# lpcCNC.net
KiCad netlist of a schematic drawn in EAGLE
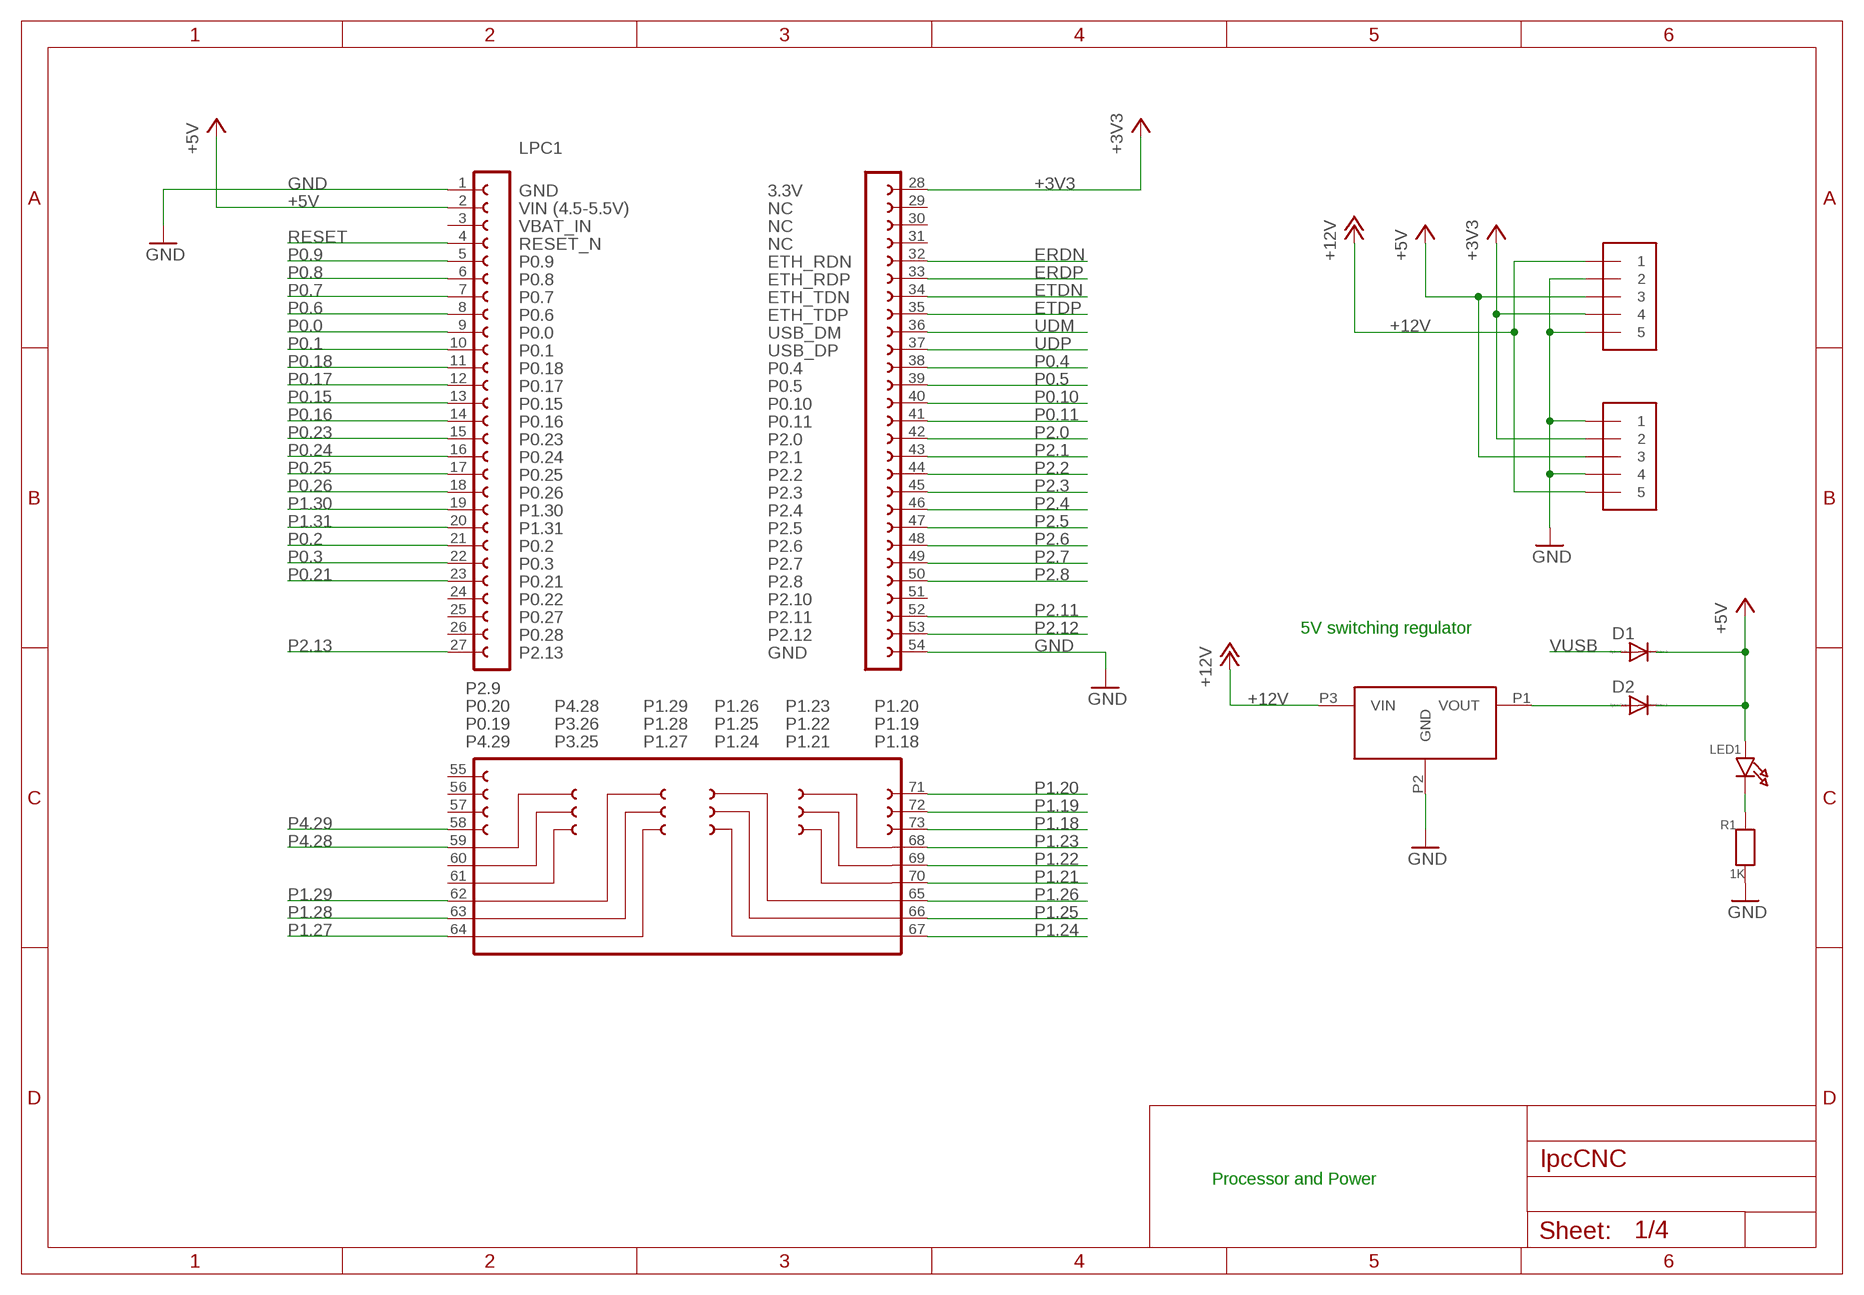
[diagram p0: schematic, sheet 1]
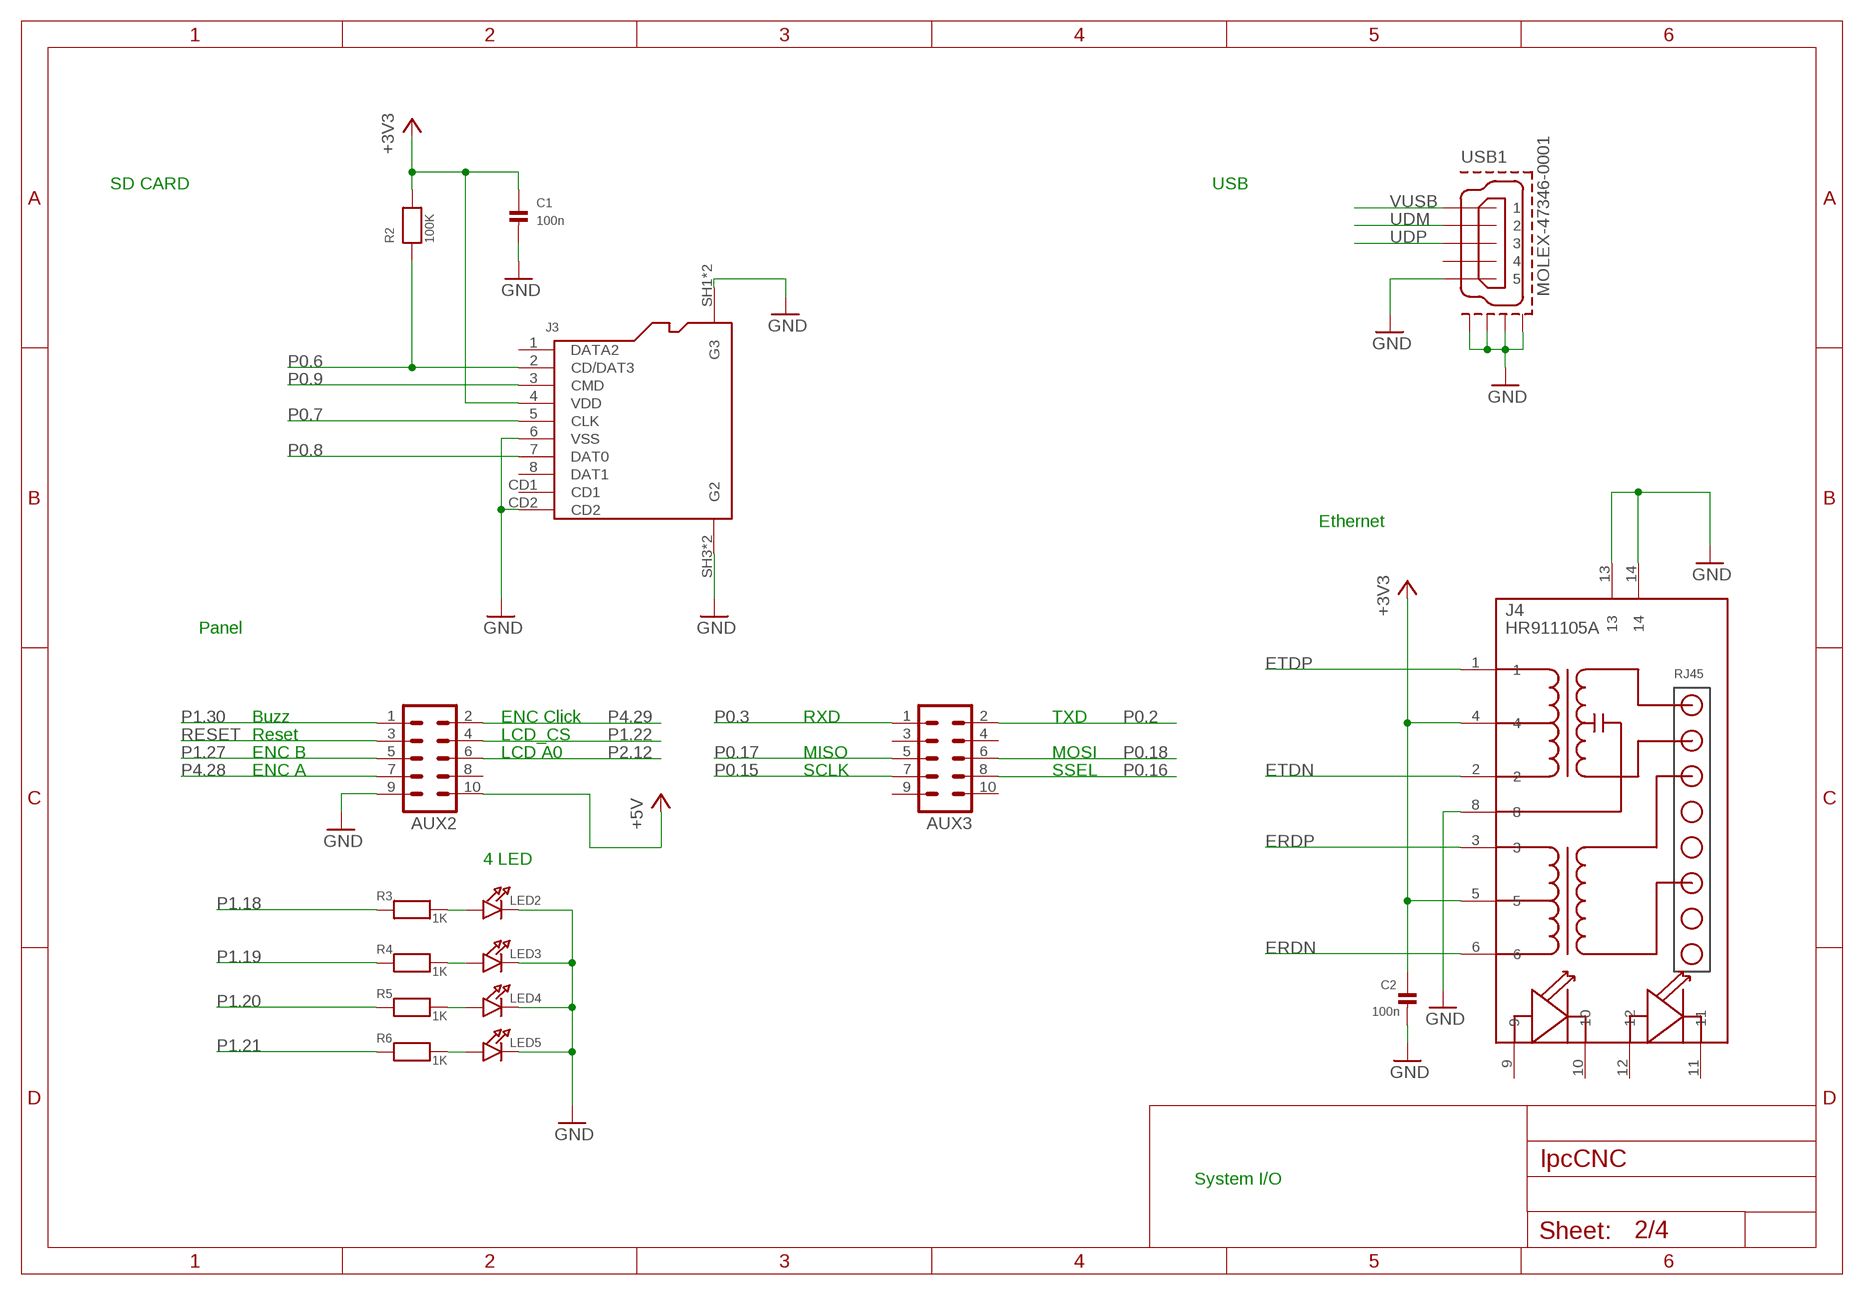
[diagram p1: schematic, sheet 2]
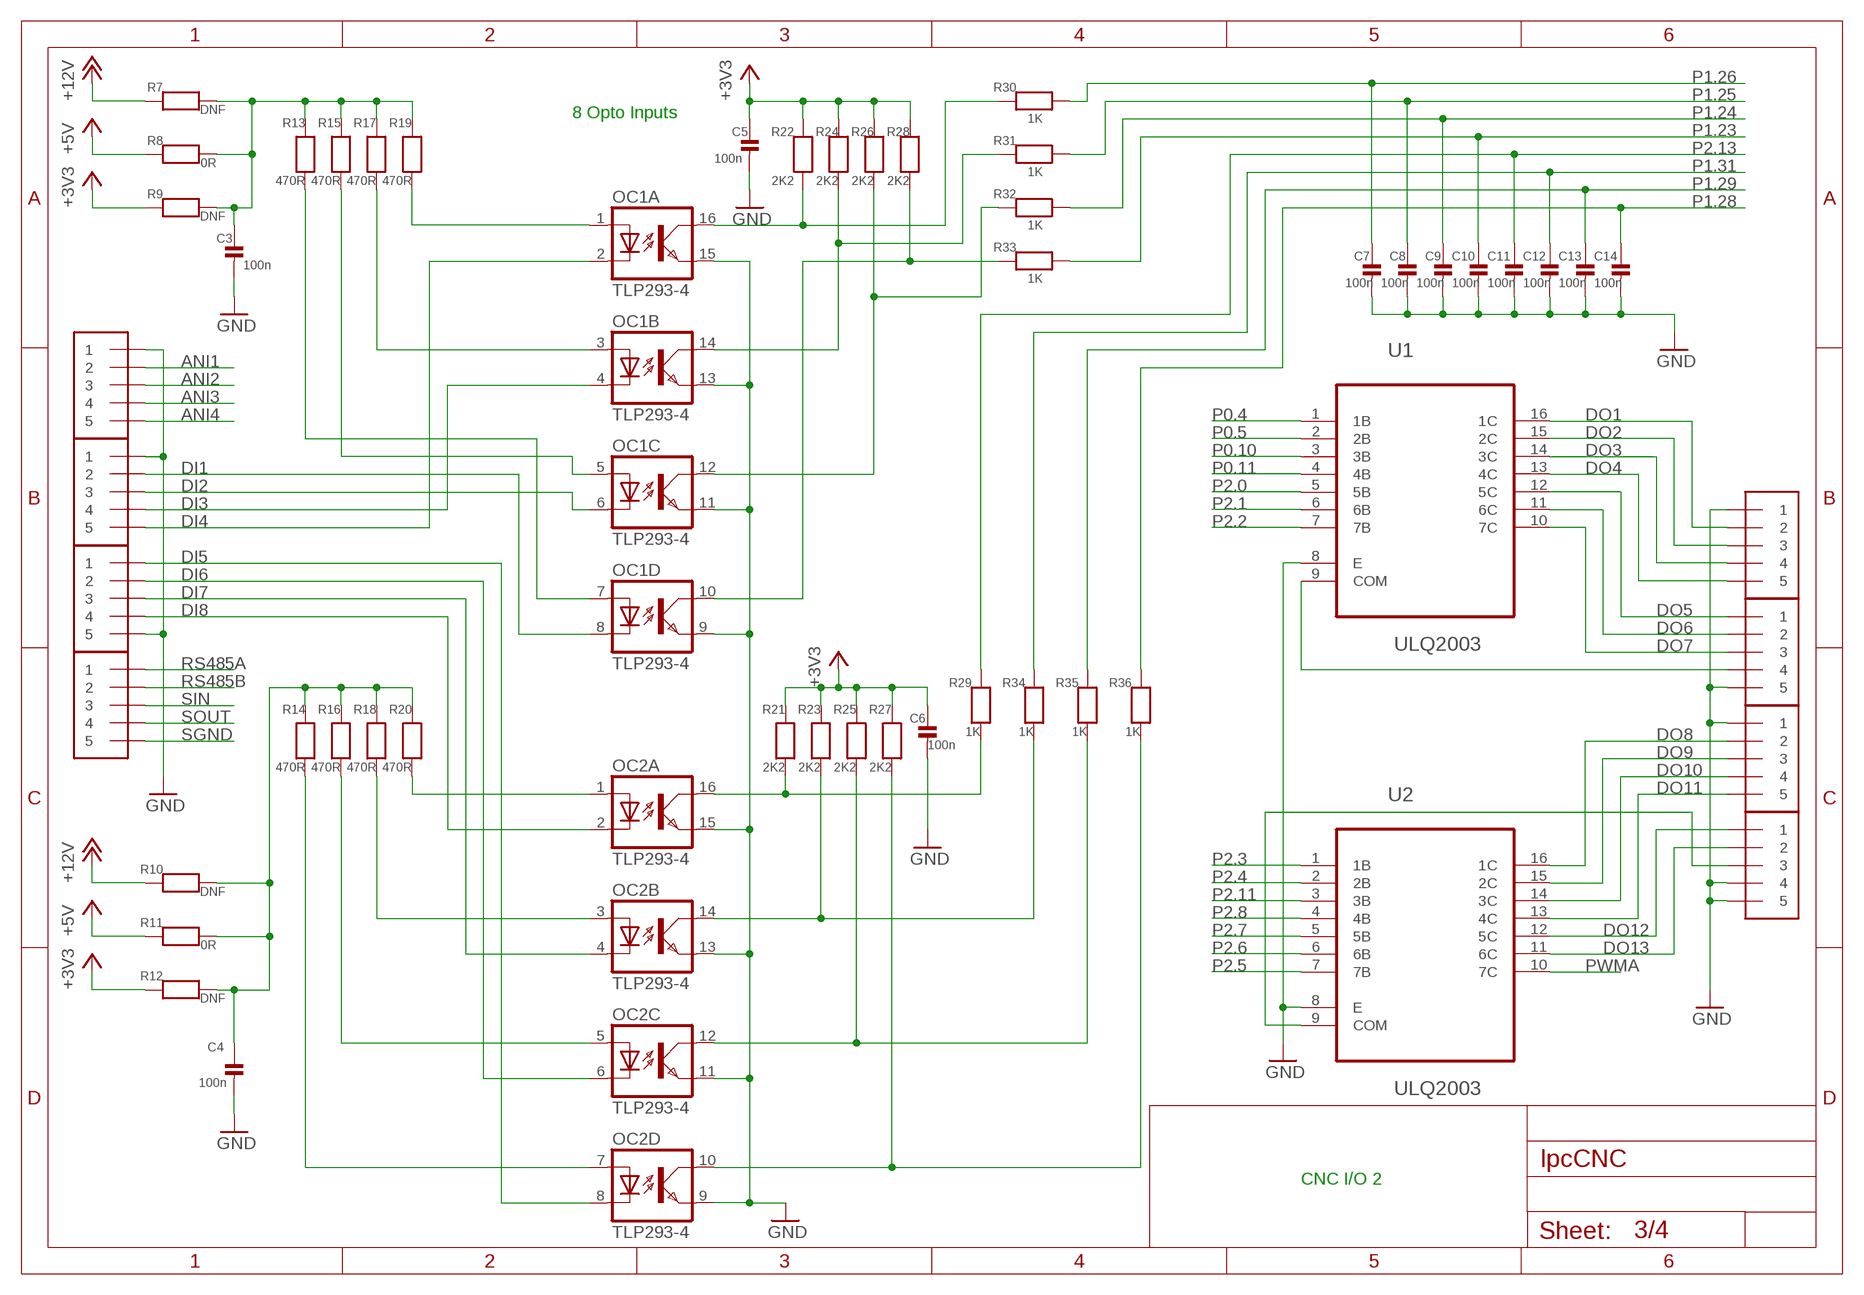
[diagram p2: schematic, sheet 3]
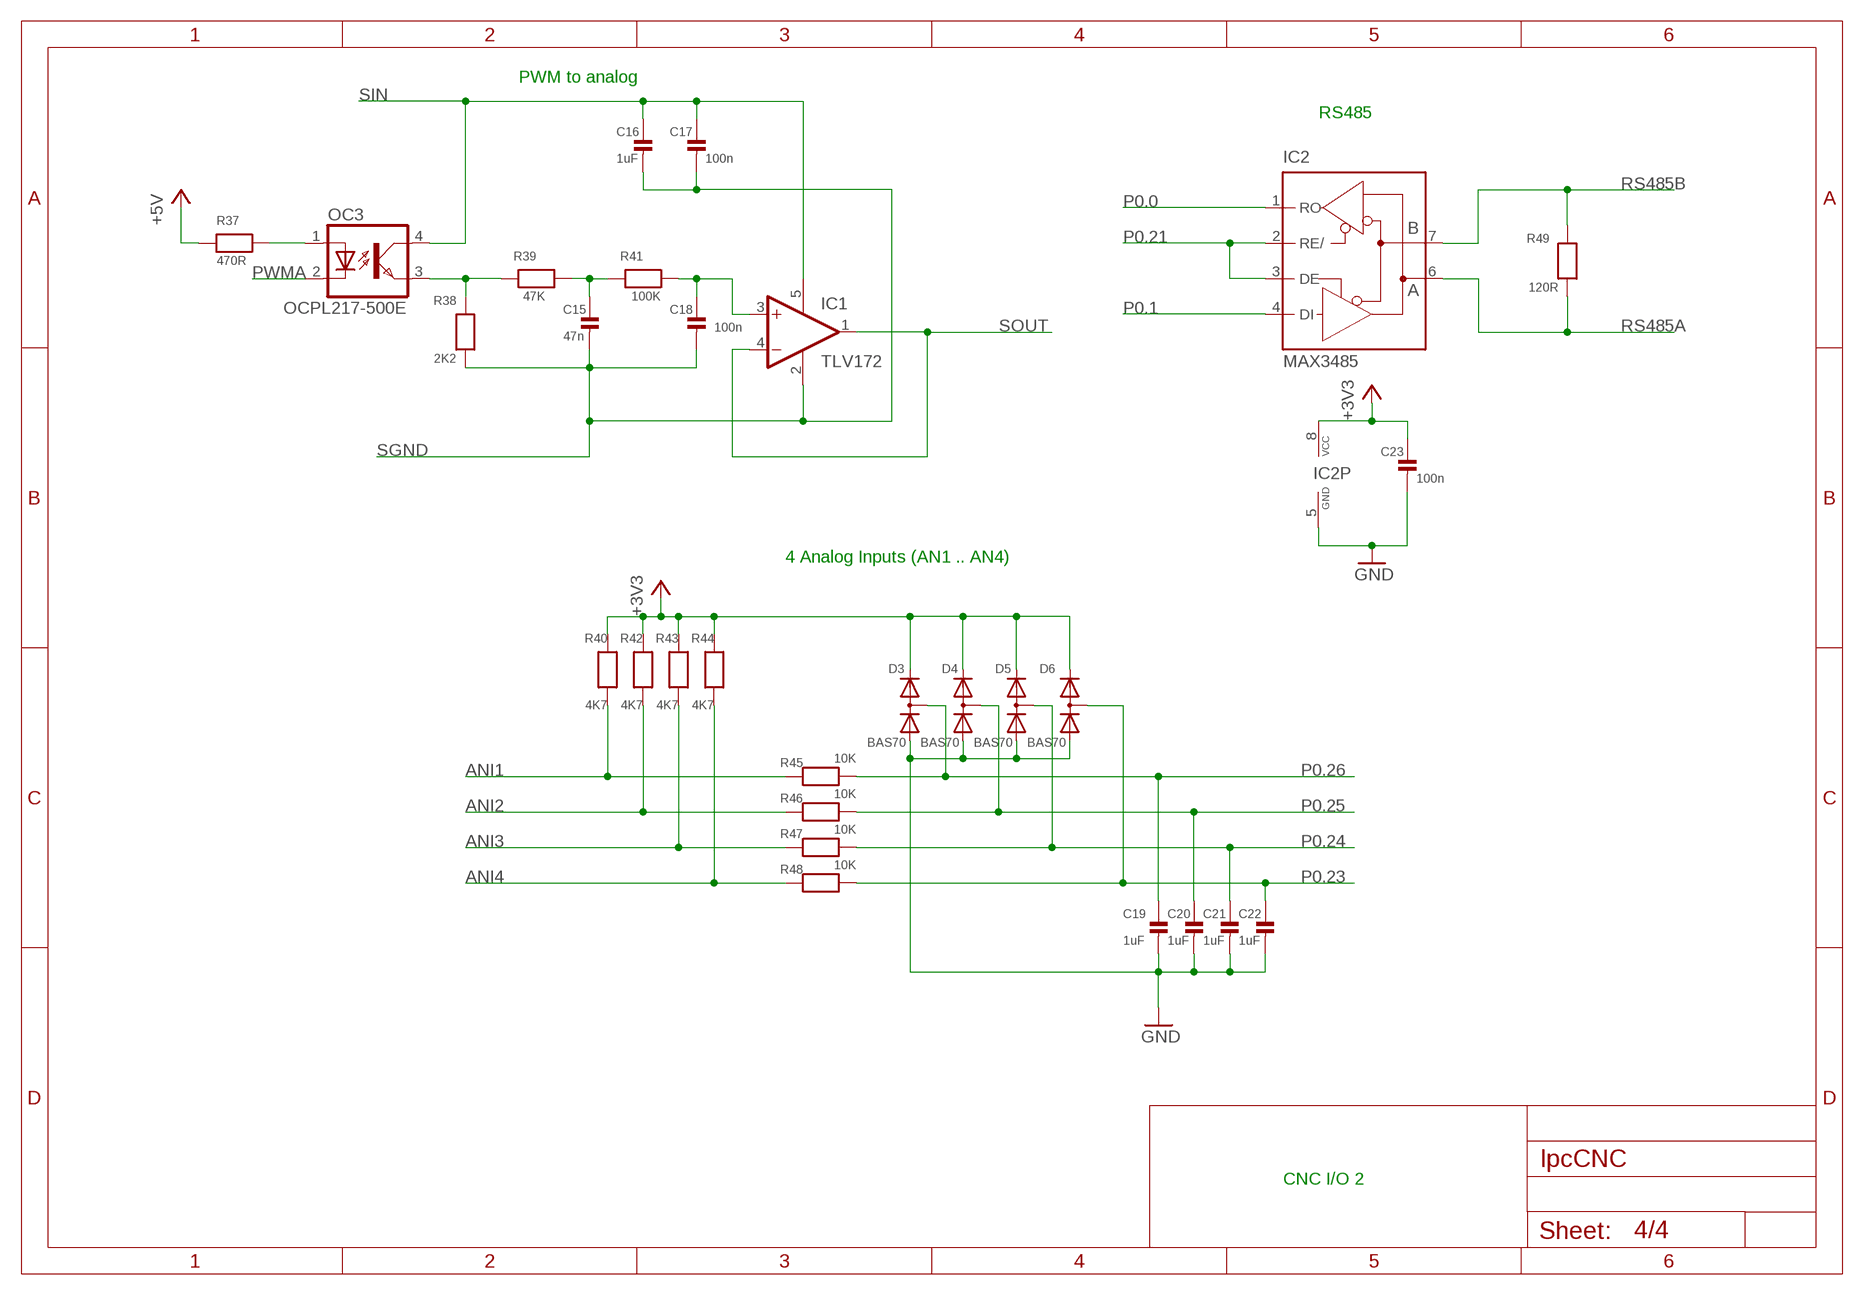
[diagram p3: schematic, sheet 4]

(export (version "E")
  (design (tool "Eeschema 10.0.6"))
  (components
    (comp (ref "C3")
      (value "100n")
      (footprint "eagle-import:0603")
      (libsource (lib "eagle-import") (part "CAP_CERAMIC0603"))
    )
    (comp (ref "C4")
      (value "100n")
      (footprint "eagle-import:0603")
      (libsource (lib "eagle-import") (part "CAP_CERAMIC0603"))
    )
    (comp (ref "C5")
      (value "100n")
      (footprint "eagle-import:0603")
      (libsource (lib "eagle-import") (part "CAP_CERAMIC0603"))
    )
    (comp (ref "C6")
      (value "100n")
      (footprint "eagle-import:0603")
      (libsource (lib "eagle-import") (part "CAP_CERAMIC0603"))
    )
    (comp (ref "C7")
      (value "100n")
      (footprint "eagle-import:0603")
      (libsource (lib "eagle-import") (part "CAP_CERAMIC0603"))
    )
    (comp (ref "C8")
      (value "100n")
      (footprint "eagle-import:0603")
      (libsource (lib "eagle-import") (part "CAP_CERAMIC0603"))
    )
    (comp (ref "C9")
      (value "100n")
      (footprint "eagle-import:0603")
      (libsource (lib "eagle-import") (part "CAP_CERAMIC0603"))
    )
    (comp (ref "C10")
      (value "100n")
      (footprint "eagle-import:0603")
      (libsource (lib "eagle-import") (part "CAP_CERAMIC0603"))
    )
    (comp (ref "C11")
      (value "100n")
      (footprint "eagle-import:0603")
      (libsource (lib "eagle-import") (part "CAP_CERAMIC0603"))
    )
    (comp (ref "C12")
      (value "100n")
      (footprint "eagle-import:0603")
      (libsource (lib "eagle-import") (part "CAP_CERAMIC0603"))
    )
    (comp (ref "C13")
      (value "100n")
      (footprint "eagle-import:0603")
      (libsource (lib "eagle-import") (part "CAP_CERAMIC0603"))
    )
    (comp (ref "C14")
      (value "100n")
      (footprint "eagle-import:0603")
      (libsource (lib "eagle-import") (part "CAP_CERAMIC0603"))
    )
    (comp (ref "J5")
      (value "1X5")
      (footprint "eagle-import:1X05-3.5MM")
      (libsource (lib "eagle-import") (part "1X5"))
    )
    (comp (ref "J6")
      (value "1X5")
      (footprint "eagle-import:1X05-3.5MM")
      (libsource (lib "eagle-import") (part "1X5"))
    )
    (comp (ref "J7")
      (value "1X5")
      (footprint "eagle-import:1X05-3.5MM")
      (libsource (lib "eagle-import") (part "1X5"))
    )
    (comp (ref "J8")
      (value "1X5")
      (footprint "eagle-import:1X05-3.5MM")
      (libsource (lib "eagle-import") (part "1X5"))
    )
    (comp (ref "J9")
      (value "1X5")
      (footprint "eagle-import:1X05-3.5MM")
      (libsource (lib "eagle-import") (part "1X5"))
    )
    (comp (ref "J10")
      (value "1X5")
      (footprint "eagle-import:1X05-3.5MM")
      (libsource (lib "eagle-import") (part "1X5"))
    )
    (comp (ref "J11")
      (value "1X5")
      (footprint "eagle-import:1X05-3.5MM")
      (libsource (lib "eagle-import") (part "1X5"))
    )
    (comp (ref "J12")
      (value "1X5")
      (footprint "eagle-import:1X05-3.5MM")
      (libsource (lib "eagle-import") (part "1X5"))
    )
    (comp (ref "OC1")
      (value "TLP293-4")
      (footprint "eagle-import:MINI-FLAT-16")
      (libsource (lib "eagle-import") (part "TLP283-4"))
    )
    (comp (ref "OC2")
      (value "TLP293-4")
      (footprint "eagle-import:MINI-FLAT-16")
      (libsource (lib "eagle-import") (part "TLP283-4"))
    )
    (comp (ref "R7")
      (value "DNF")
      (footprint "eagle-import:0603")
      (libsource (lib "eagle-import") (part "RESISTOR0603"))
    )
    (comp (ref "R8")
      (value "0R")
      (footprint "eagle-import:0603")
      (libsource (lib "eagle-import") (part "RESISTOR0603"))
    )
    (comp (ref "R9")
      (value "DNF")
      (footprint "eagle-import:0603")
      (libsource (lib "eagle-import") (part "RESISTOR0603"))
    )
    (comp (ref "R10")
      (value "DNF")
      (footprint "eagle-import:0603")
      (libsource (lib "eagle-import") (part "RESISTOR0603"))
    )
    (comp (ref "R11")
      (value "0R")
      (footprint "eagle-import:0603")
      (libsource (lib "eagle-import") (part "RESISTOR0603"))
    )
    (comp (ref "R12")
      (value "DNF")
      (footprint "eagle-import:0603")
      (libsource (lib "eagle-import") (part "RESISTOR0603"))
    )
    (comp (ref "R13")
      (value "470R")
      (footprint "eagle-import:0603")
      (libsource (lib "eagle-import") (part "RESISTOR0603"))
    )
    (comp (ref "R14")
      (value "470R")
      (footprint "eagle-import:0603")
      (libsource (lib "eagle-import") (part "RESISTOR0603"))
    )
    (comp (ref "R15")
      (value "470R")
      (footprint "eagle-import:0603")
      (libsource (lib "eagle-import") (part "RESISTOR0603"))
    )
    (comp (ref "R16")
      (value "470R")
      (footprint "eagle-import:0603")
      (libsource (lib "eagle-import") (part "RESISTOR0603"))
    )
    (comp (ref "R17")
      (value "470R")
      (footprint "eagle-import:0603")
      (libsource (lib "eagle-import") (part "RESISTOR0603"))
    )
    (comp (ref "R18")
      (value "470R")
      (footprint "eagle-import:0603")
      (libsource (lib "eagle-import") (part "RESISTOR0603"))
    )
    (comp (ref "R19")
      (value "470R")
      (footprint "eagle-import:0603")
      (libsource (lib "eagle-import") (part "RESISTOR0603"))
    )
    (comp (ref "R20")
      (value "470R")
      (footprint "eagle-import:0603")
      (libsource (lib "eagle-import") (part "RESISTOR0603"))
    )
    (comp (ref "R21")
      (value "2K2")
      (footprint "eagle-import:0603")
      (libsource (lib "eagle-import") (part "RESISTOR0603"))
    )
    (comp (ref "R22")
      (value "2K2")
      (footprint "eagle-import:0603")
      (libsource (lib "eagle-import") (part "RESISTOR0603"))
    )
    (comp (ref "R23")
      (value "2K2")
      (footprint "eagle-import:0603")
      (libsource (lib "eagle-import") (part "RESISTOR0603"))
    )
    (comp (ref "R24")
      (value "2K2")
      (footprint "eagle-import:0603")
      (libsource (lib "eagle-import") (part "RESISTOR0603"))
    )
    (comp (ref "R25")
      (value "2K2")
      (footprint "eagle-import:0603")
      (libsource (lib "eagle-import") (part "RESISTOR0603"))
    )
    (comp (ref "R26")
      (value "2K2")
      (footprint "eagle-import:0603")
      (libsource (lib "eagle-import") (part "RESISTOR0603"))
    )
    (comp (ref "R27")
      (value "2K2")
      (footprint "eagle-import:0603")
      (libsource (lib "eagle-import") (part "RESISTOR0603"))
    )
    (comp (ref "R28")
      (value "2K2")
      (footprint "eagle-import:0603")
      (libsource (lib "eagle-import") (part "RESISTOR0603"))
    )
    (comp (ref "R29")
      (value "1K")
      (footprint "eagle-import:0603")
      (libsource (lib "eagle-import") (part "RESISTOR0603"))
    )
    (comp (ref "R30")
      (value "1K")
      (footprint "eagle-import:0603")
      (libsource (lib "eagle-import") (part "RESISTOR0603"))
    )
    (comp (ref "R31")
      (value "1K")
      (footprint "eagle-import:0603")
      (libsource (lib "eagle-import") (part "RESISTOR0603"))
    )
    (comp (ref "R32")
      (value "1K")
      (footprint "eagle-import:0603")
      (libsource (lib "eagle-import") (part "RESISTOR0603"))
    )
    (comp (ref "R33")
      (value "1K")
      (footprint "eagle-import:0603")
      (libsource (lib "eagle-import") (part "RESISTOR0603"))
    )
    (comp (ref "R34")
      (value "1K")
      (footprint "eagle-import:0603")
      (libsource (lib "eagle-import") (part "RESISTOR0603"))
    )
    (comp (ref "R35")
      (value "1K")
      (footprint "eagle-import:0603")
      (libsource (lib "eagle-import") (part "RESISTOR0603"))
    )
    (comp (ref "R36")
      (value "1K")
      (footprint "eagle-import:0603")
      (libsource (lib "eagle-import") (part "RESISTOR0603"))
    )
    (comp (ref "U1")
      (value "ULQ2003")
      (footprint "eagle-import:SOIC127P600X175-16N")
      (fields (field (name "MPN") "ULN2003ADE4"))
      (libsource (lib "eagle-import") (part "ULN2003ADE4"))
    )
    (comp (ref "U2")
      (value "ULQ2003")
      (footprint "eagle-import:SOIC127P600X175-16N")
      (fields (field (name "MPN") "ULN2003ADE4"))
      (libsource (lib "eagle-import") (part "ULN2003ADE4"))
    )
    (comp (ref "C15")
      (value "47n")
      (footprint "eagle-import:0603")
      (libsource (lib "eagle-import") (part "CAP_CERAMIC0603"))
    )
    (comp (ref "C16")
      (value "1uF")
      (footprint "eagle-import:0603")
      (libsource (lib "eagle-import") (part "CAP_CERAMIC0603"))
    )
    (comp (ref "C17")
      (value "100n")
      (footprint "eagle-import:0603")
      (libsource (lib "eagle-import") (part "CAP_CERAMIC0603"))
    )
    (comp (ref "C18")
      (value "100n")
      (footprint "eagle-import:0603")
      (libsource (lib "eagle-import") (part "CAP_CERAMIC0603"))
    )
    (comp (ref "C19")
      (value "1uF")
      (footprint "eagle-import:0603")
      (libsource (lib "eagle-import") (part "CAP_CERAMIC0603"))
    )
    (comp (ref "C20")
      (value "1uF")
      (footprint "eagle-import:0603")
      (libsource (lib "eagle-import") (part "CAP_CERAMIC0603"))
    )
    (comp (ref "C21")
      (value "1uF")
      (footprint "eagle-import:0603")
      (libsource (lib "eagle-import") (part "CAP_CERAMIC0603"))
    )
    (comp (ref "C22")
      (value "1uF")
      (footprint "eagle-import:0603")
      (libsource (lib "eagle-import") (part "CAP_CERAMIC0603"))
    )
    (comp (ref "C23")
      (value "100n")
      (footprint "eagle-import:0603")
      (libsource (lib "eagle-import") (part "CAP_CERAMIC0603"))
    )
    (comp (ref "D3")
      (value "BAS70")
      (footprint "eagle-import:SOT23")
      (libsource (lib "eagle-import") (part "DIODE_2CACA-SOT23"))
    )
    (comp (ref "D4")
      (value "BAS70")
      (footprint "eagle-import:SOT23")
      (libsource (lib "eagle-import") (part "DIODE_2CACA-SOT23"))
    )
    (comp (ref "D5")
      (value "BAS70")
      (footprint "eagle-import:SOT23")
      (libsource (lib "eagle-import") (part "DIODE_2CACA-SOT23"))
    )
    (comp (ref "D6")
      (value "BAS70")
      (footprint "eagle-import:SOT23")
      (libsource (lib "eagle-import") (part "DIODE_2CACA-SOT23"))
    )
    (comp (ref "IC1")
      (value "TLV172")
      (footprint "eagle-import:SOT23-5")
      (libsource (lib "eagle-import") (part "TLV172MF"))
    )
    (comp (ref "IC2")
      (value "MAX3485")
      (footprint "eagle-import:SO08")
      (fields (field (name "MF") "MAXIM") (field (name "MPN") "MAX481CSA"))
      (libsource (lib "eagle-import") (part "MAX481CSA"))
    )
    (comp (ref "OC3")
      (value "OCPL217-500E")
      (footprint "eagle-import:MINI-FLAT-4")
      (libsource (lib "eagle-import") (part "TLP283"))
    )
    (comp (ref "R37")
      (value "470R")
      (footprint "eagle-import:0603")
      (libsource (lib "eagle-import") (part "RESISTOR0603"))
    )
    (comp (ref "R38")
      (value "2K2")
      (footprint "eagle-import:0603")
      (libsource (lib "eagle-import") (part "RESISTOR0603"))
    )
    (comp (ref "R39")
      (value "47K")
      (footprint "eagle-import:0603")
      (libsource (lib "eagle-import") (part "RESISTOR0603"))
    )
    (comp (ref "R40")
      (value "4K7")
      (footprint "eagle-import:0603")
      (libsource (lib "eagle-import") (part "RESISTOR0603"))
    )
    (comp (ref "R41")
      (value "100K")
      (footprint "eagle-import:0603")
      (libsource (lib "eagle-import") (part "RESISTOR0603"))
    )
    (comp (ref "R42")
      (value "4K7")
      (footprint "eagle-import:0603")
      (libsource (lib "eagle-import") (part "RESISTOR0603"))
    )
    (comp (ref "R43")
      (value "4K7")
      (footprint "eagle-import:0603")
      (libsource (lib "eagle-import") (part "RESISTOR0603"))
    )
    (comp (ref "R44")
      (value "4K7")
      (footprint "eagle-import:0603")
      (libsource (lib "eagle-import") (part "RESISTOR0603"))
    )
    (comp (ref "R45")
      (value "10K")
      (footprint "eagle-import:0603")
      (libsource (lib "eagle-import") (part "RESISTOR0603"))
    )
    (comp (ref "R46")
      (value "10K")
      (footprint "eagle-import:0603")
      (libsource (lib "eagle-import") (part "RESISTOR0603"))
    )
    (comp (ref "R47")
      (value "10K")
      (footprint "eagle-import:0603")
      (libsource (lib "eagle-import") (part "RESISTOR0603"))
    )
    (comp (ref "R48")
      (value "10K")
      (footprint "eagle-import:0603")
      (libsource (lib "eagle-import") (part "RESISTOR0603"))
    )
    (comp (ref "R49")
      (value "120R")
      (footprint "eagle-import:0603")
      (libsource (lib "eagle-import") (part "RESISTOR0603"))
    )
    (comp (ref "D1")
      (value "DIODE-DO-214AC")
      (footprint "eagle-import:DO-214AC")
      (libsource (lib "eagle-import") (part "DIODE-DO-214AC"))
    )
    (comp (ref "D2")
      (value "DIODE-DO-214AC")
      (footprint "eagle-import:DO-214AC")
      (libsource (lib "eagle-import") (part "DIODE-DO-214AC"))
    )
    (comp (ref "J1")
      (value "1X5")
      (footprint "eagle-import:1X05-3.5MM")
      (libsource (lib "eagle-import") (part "1X5"))
    )
    (comp (ref "J2")
      (value "1X5")
      (footprint "eagle-import:1X05-3.5MM")
      (libsource (lib "eagle-import") (part "1X5"))
    )
    (comp (ref "LED1")
      (value "LED0603")
      (footprint "eagle-import:CHIPLED_0603")
      (libsource (lib "eagle-import") (part "LED0603"))
    )
    (comp (ref "LPC1")
      (value "LPCXPRESSO_LPC1769")
      (footprint "eagle-import:LPCXPRESSO_LPC1769")
      (libsource (lib "eagle-import") (part "LPCXPRESSO_LPC1769"))
    )
    (comp (ref "R1")
      (value "1K")
      (footprint "eagle-import:0603")
      (libsource (lib "eagle-import") (part "RESISTOR0603"))
    )
    (comp (ref "VR1")
      (value "78SR")
      (footprint "eagle-import:78SR")
      (libsource (lib "eagle-import") (part "78SR"))
    )
    (comp (ref "AUX2")
      (value "ML10")
      (footprint "eagle-import:ML10")
      (libsource (lib "eagle-import") (part "ML10"))
    )
    (comp (ref "AUX3")
      (value "ML10")
      (footprint "eagle-import:ML10")
      (libsource (lib "eagle-import") (part "ML10"))
    )
    (comp (ref "C1")
      (value "100n")
      (footprint "eagle-import:0603")
      (libsource (lib "eagle-import") (part "CAP_CERAMIC0603"))
    )
    (comp (ref "C2")
      (value "100n")
      (footprint "eagle-import:0603")
      (libsource (lib "eagle-import") (part "CAP_CERAMIC0603"))
    )
    (comp (ref "J3")
      (value "AMPHENOL_114-00841-68")
      (footprint "eagle-import:AMPHENOL_114-00841-68")
      (libsource (lib "eagle-import") (part "AMPHENOL_114-00841-68"))
    )
    (comp (ref "J4")
      (value "HR911105A")
      (footprint "eagle-import:HR911105A")
      (libsource (lib "eagle-import") (part "HR911105A"))
    )
    (comp (ref "LED2")
      (value "LED0603")
      (footprint "eagle-import:CHIPLED_0603")
      (libsource (lib "eagle-import") (part "LED0603"))
    )
    (comp (ref "LED3")
      (value "LED0603")
      (footprint "eagle-import:CHIPLED_0603")
      (libsource (lib "eagle-import") (part "LED0603"))
    )
    (comp (ref "LED4")
      (value "LED0603")
      (footprint "eagle-import:CHIPLED_0603")
      (libsource (lib "eagle-import") (part "LED0603"))
    )
    (comp (ref "LED5")
      (value "LED0603")
      (footprint "eagle-import:CHIPLED_0603")
      (libsource (lib "eagle-import") (part "LED0603"))
    )
    (comp (ref "R2")
      (value "100K")
      (footprint "eagle-import:0603")
      (libsource (lib "eagle-import") (part "RESISTOR0603"))
    )
    (comp (ref "R3")
      (value "1K")
      (footprint "eagle-import:0603")
      (libsource (lib "eagle-import") (part "RESISTOR0603"))
    )
    (comp (ref "R4")
      (value "1K")
      (footprint "eagle-import:0603")
      (libsource (lib "eagle-import") (part "RESISTOR0603"))
    )
    (comp (ref "R5")
      (value "1K")
      (footprint "eagle-import:0603")
      (libsource (lib "eagle-import") (part "RESISTOR0603"))
    )
    (comp (ref "R6")
      (value "1K")
      (footprint "eagle-import:0603")
      (libsource (lib "eagle-import") (part "RESISTOR0603"))
    )
    (comp (ref "USB1")
      (value "MOLEX-47346-0001")
      (footprint "eagle-import:MOLEX-47364-0001")
      (libsource (lib "eagle-import") (part "MOLEX-47346-0001"))
    )
  )
  (nets
    (net (code "1") (name "+3V3") (class "Default")
      (node (ref "C1") (pin "1") (pinfunction "P$1_1") (pintype "passive"))
      (node (ref "C2") (pin "1") (pinfunction "P$1_1") (pintype "passive"))
      (node (ref "C23") (pin "1") (pinfunction "P$1_1") (pintype "passive"))
      (node (ref "C5") (pin "1") (pinfunction "P$1_1") (pintype "passive"))
      (node (ref "C6") (pin "1") (pinfunction "P$1_1") (pintype "passive"))
      (node (ref "D3") (pin "2") (pinfunction "C_2") (pintype "passive"))
      (node (ref "D4") (pin "2") (pinfunction "C_2") (pintype "passive"))
      (node (ref "D5") (pin "2") (pinfunction "C_2") (pintype "passive"))
      (node (ref "D6") (pin "2") (pinfunction "C_2") (pintype "passive"))
      (node (ref "IC2") (pin "8") (pinfunction "VCC_8") (pintype "power_in"))
      (node (ref "J1") (pin "4") (pinfunction "4_4") (pintype "passive"))
      (node (ref "J2") (pin "2") (pinfunction "2_2") (pintype "passive"))
      (node (ref "J3") (pin "4") (pinfunction "VDD_4") (pintype "power_in"))
      (node (ref "J4") (pin "4") (pinfunction "4_4") (pintype "bidirectional"))
      (node (ref "J4") (pin "5") (pinfunction "5_5") (pintype "bidirectional"))
      (node (ref "LPC1") (pin "28") (pinfunction "28_28") (pintype "passive"))
      (node (ref "R12") (pin "2") (pinfunction "2_2") (pintype "passive"))
      (node (ref "R2") (pin "2") (pinfunction "2_2") (pintype "passive"))
      (node (ref "R21") (pin "2") (pinfunction "2_2") (pintype "passive"))
      (node (ref "R22") (pin "2") (pinfunction "2_2") (pintype "passive"))
      (node (ref "R23") (pin "2") (pinfunction "2_2") (pintype "passive"))
      (node (ref "R24") (pin "2") (pinfunction "2_2") (pintype "passive"))
      (node (ref "R25") (pin "2") (pinfunction "2_2") (pintype "passive"))
      (node (ref "R26") (pin "2") (pinfunction "2_2") (pintype "passive"))
      (node (ref "R27") (pin "2") (pinfunction "2_2") (pintype "passive"))
      (node (ref "R28") (pin "2") (pinfunction "2_2") (pintype "passive"))
      (node (ref "R40") (pin "2") (pinfunction "2_2") (pintype "passive"))
      (node (ref "R42") (pin "2") (pinfunction "2_2") (pintype "passive"))
      (node (ref "R43") (pin "2") (pinfunction "2_2") (pintype "passive"))
      (node (ref "R44") (pin "2") (pinfunction "2_2") (pintype "passive"))
      (node (ref "R9") (pin "2") (pinfunction "2_2") (pintype "passive"))
    )
    (net (code "2") (name "+5V") (class "Default")
      (node (ref "AUX2") (pin "10") (pinfunction "10_10") (pintype "passive"))
      (node (ref "D1") (pin "C") (pinfunction "C_C") (pintype "passive"))
      (node (ref "D2") (pin "C") (pinfunction "C_C") (pintype "passive"))
      (node (ref "J1") (pin "3") (pinfunction "3_3") (pintype "passive"))
      (node (ref "J2") (pin "3") (pinfunction "3_3") (pintype "passive"))
      (node (ref "LED1") (pin "A") (pinfunction "A_A") (pintype "passive"))
      (node (ref "LPC1") (pin "2") (pinfunction "2_2") (pintype "passive"))
      (node (ref "R11") (pin "2") (pinfunction "2_2") (pintype "passive"))
      (node (ref "R37") (pin "1") (pinfunction "1_1") (pintype "passive"))
      (node (ref "R8") (pin "2") (pinfunction "2_2") (pintype "passive"))
    )
    (net (code "3") (name "+12V") (class "Default")
      (node (ref "J1") (pin "1") (pinfunction "1_1") (pintype "passive"))
      (node (ref "J2") (pin "5") (pinfunction "5_5") (pintype "passive"))
      (node (ref "R10") (pin "2") (pinfunction "2_2") (pintype "passive"))
      (node (ref "R7") (pin "2") (pinfunction "2_2") (pintype "passive"))
      (node (ref "VR1") (pin "P3") (pinfunction "VIN_P3") (pintype "bidirectional"))
    )
    (net (code "4") (name "ANI1") (class "Default")
      (node (ref "J5") (pin "2") (pinfunction "2_2") (pintype "passive"))
      (node (ref "R40") (pin "1") (pinfunction "1_1") (pintype "passive"))
      (node (ref "R45") (pin "2") (pinfunction "2_2") (pintype "passive"))
    )
    (net (code "5") (name "ANI2") (class "Default")
      (node (ref "J5") (pin "3") (pinfunction "3_3") (pintype "passive"))
      (node (ref "R42") (pin "1") (pinfunction "1_1") (pintype "passive"))
      (node (ref "R46") (pin "2") (pinfunction "2_2") (pintype "passive"))
    )
    (net (code "6") (name "ANI3") (class "Default")
      (node (ref "J5") (pin "4") (pinfunction "4_4") (pintype "passive"))
      (node (ref "R43") (pin "1") (pinfunction "1_1") (pintype "passive"))
      (node (ref "R47") (pin "2") (pinfunction "2_2") (pintype "passive"))
    )
    (net (code "7") (name "ANI4") (class "Default")
      (node (ref "J5") (pin "5") (pinfunction "5_5") (pintype "passive"))
      (node (ref "R44") (pin "1") (pinfunction "1_1") (pintype "passive"))
      (node (ref "R48") (pin "2") (pinfunction "2_2") (pintype "passive"))
    )
    (net (code "8") (name "DI1") (class "Default")
      (node (ref "J6") (pin "2") (pinfunction "2_2") (pintype "passive"))
      (node (ref "OC1") (pin "8") (pinfunction "C_8") (pintype "passive"))
    )
    (net (code "9") (name "DI2") (class "Default")
      (node (ref "J6") (pin "3") (pinfunction "3_3") (pintype "passive"))
      (node (ref "OC1") (pin "6") (pinfunction "C_6") (pintype "passive"))
    )
    (net (code "10") (name "DI3") (class "Default")
      (node (ref "J6") (pin "4") (pinfunction "4_4") (pintype "passive"))
      (node (ref "OC1") (pin "4") (pinfunction "C_4") (pintype "passive"))
    )
    (net (code "11") (name "DI4") (class "Default")
      (node (ref "J6") (pin "5") (pinfunction "5_5") (pintype "passive"))
      (node (ref "OC1") (pin "2") (pinfunction "C_2") (pintype "passive"))
    )
    (net (code "12") (name "DI5") (class "Default")
      (node (ref "J7") (pin "1") (pinfunction "1_1") (pintype "passive"))
      (node (ref "OC2") (pin "8") (pinfunction "C_8") (pintype "passive"))
    )
    (net (code "13") (name "DI6") (class "Default")
      (node (ref "J7") (pin "2") (pinfunction "2_2") (pintype "passive"))
      (node (ref "OC2") (pin "6") (pinfunction "C_6") (pintype "passive"))
    )
    (net (code "14") (name "DI7") (class "Default")
      (node (ref "J7") (pin "3") (pinfunction "3_3") (pintype "passive"))
      (node (ref "OC2") (pin "4") (pinfunction "C_4") (pintype "passive"))
    )
    (net (code "15") (name "DI8") (class "Default")
      (node (ref "J7") (pin "4") (pinfunction "4_4") (pintype "passive"))
      (node (ref "OC2") (pin "2") (pinfunction "C_2") (pintype "passive"))
    )
    (net (code "16") (name "DO1") (class "Default")
      (node (ref "J9") (pin "2") (pinfunction "2_2") (pintype "passive"))
      (node (ref "U1") (pin "16") (pinfunction "1C_16") (pintype "output"))
    )
    (net (code "17") (name "DO2") (class "Default")
      (node (ref "J9") (pin "3") (pinfunction "3_3") (pintype "passive"))
      (node (ref "U1") (pin "15") (pinfunction "2C_15") (pintype "output"))
    )
    (net (code "18") (name "DO3") (class "Default")
      (node (ref "J9") (pin "4") (pinfunction "4_4") (pintype "passive"))
      (node (ref "U1") (pin "14") (pinfunction "3C_14") (pintype "output"))
    )
    (net (code "19") (name "DO4") (class "Default")
      (node (ref "J9") (pin "5") (pinfunction "5_5") (pintype "passive"))
      (node (ref "U1") (pin "13") (pinfunction "4C_13") (pintype "output"))
    )
    (net (code "20") (name "DO5") (class "Default")
      (node (ref "J10") (pin "1") (pinfunction "1_1") (pintype "passive"))
      (node (ref "U1") (pin "12") (pinfunction "5C_12") (pintype "output"))
    )
    (net (code "21") (name "DO6") (class "Default")
      (node (ref "J10") (pin "2") (pinfunction "2_2") (pintype "passive"))
      (node (ref "U1") (pin "11") (pinfunction "6C_11") (pintype "output"))
    )
    (net (code "22") (name "DO7") (class "Default")
      (node (ref "J10") (pin "3") (pinfunction "3_3") (pintype "passive"))
      (node (ref "U1") (pin "10") (pinfunction "7C_10") (pintype "output"))
    )
    (net (code "23") (name "DO8") (class "Default")
      (node (ref "J11") (pin "2") (pinfunction "2_2") (pintype "passive"))
      (node (ref "U2") (pin "16") (pinfunction "1C_16") (pintype "output"))
    )
    (net (code "24") (name "DO9") (class "Default")
      (node (ref "J11") (pin "3") (pinfunction "3_3") (pintype "passive"))
      (node (ref "U2") (pin "15") (pinfunction "2C_15") (pintype "output"))
    )
    (net (code "25") (name "DO10") (class "Default")
      (node (ref "J11") (pin "4") (pinfunction "4_4") (pintype "passive"))
      (node (ref "U2") (pin "14") (pinfunction "3C_14") (pintype "output"))
    )
    (net (code "26") (name "DO11") (class "Default")
      (node (ref "J11") (pin "5") (pinfunction "5_5") (pintype "passive"))
      (node (ref "U2") (pin "13") (pinfunction "4C_13") (pintype "output"))
    )
    (net (code "27") (name "DO12") (class "Default")
      (node (ref "J12") (pin "1") (pinfunction "1_1") (pintype "passive"))
      (node (ref "U2") (pin "12") (pinfunction "5C_12") (pintype "output"))
    )
    (net (code "28") (name "DO13") (class "Default")
      (node (ref "J12") (pin "2") (pinfunction "2_2") (pintype "passive"))
      (node (ref "U2") (pin "11") (pinfunction "6C_11") (pintype "output"))
    )
    (net (code "29") (name "ERDN") (class "Default")
      (node (ref "J4") (pin "6") (pinfunction "6_6") (pintype "bidirectional"))
      (node (ref "LPC1") (pin "32") (pinfunction "32_32") (pintype "passive"))
    )
    (net (code "30") (name "ERDP") (class "Default")
      (node (ref "J4") (pin "3") (pinfunction "3_3") (pintype "bidirectional"))
      (node (ref "LPC1") (pin "33") (pinfunction "33_33") (pintype "passive"))
    )
    (net (code "31") (name "ETDN") (class "Default")
      (node (ref "J4") (pin "2") (pinfunction "2_2") (pintype "bidirectional"))
      (node (ref "LPC1") (pin "34") (pinfunction "34_34") (pintype "passive"))
    )
    (net (code "32") (name "ETDP") (class "Default")
      (node (ref "J4") (pin "1") (pinfunction "1_1") (pintype "bidirectional"))
      (node (ref "LPC1") (pin "35") (pinfunction "35_35") (pintype "passive"))
    )
    (net (code "33") (name "GND") (class "Default")
      (node (ref "AUX2") (pin "9") (pinfunction "9_9") (pintype "passive"))
      (node (ref "C1") (pin "2") (pinfunction "P$2_2") (pintype "passive"))
      (node (ref "C10") (pin "2") (pinfunction "P$2_2") (pintype "passive"))
      (node (ref "C11") (pin "2") (pinfunction "P$2_2") (pintype "passive"))
      (node (ref "C12") (pin "2") (pinfunction "P$2_2") (pintype "passive"))
      (node (ref "C13") (pin "2") (pinfunction "P$2_2") (pintype "passive"))
      (node (ref "C14") (pin "2") (pinfunction "P$2_2") (pintype "passive"))
      (node (ref "C19") (pin "2") (pinfunction "P$2_2") (pintype "passive"))
      (node (ref "C2") (pin "2") (pinfunction "P$2_2") (pintype "passive"))
      (node (ref "C20") (pin "2") (pinfunction "P$2_2") (pintype "passive"))
      (node (ref "C21") (pin "2") (pinfunction "P$2_2") (pintype "passive"))
      (node (ref "C22") (pin "2") (pinfunction "P$2_2") (pintype "passive"))
      (node (ref "C23") (pin "2") (pinfunction "P$2_2") (pintype "passive"))
      (node (ref "C3") (pin "2") (pinfunction "P$2_2") (pintype "passive"))
      (node (ref "C4") (pin "2") (pinfunction "P$2_2") (pintype "passive"))
      (node (ref "C5") (pin "2") (pinfunction "P$2_2") (pintype "passive"))
      (node (ref "C6") (pin "2") (pinfunction "P$2_2") (pintype "passive"))
      (node (ref "C7") (pin "2") (pinfunction "P$2_2") (pintype "passive"))
      (node (ref "C8") (pin "2") (pinfunction "P$2_2") (pintype "passive"))
      (node (ref "C9") (pin "2") (pinfunction "P$2_2") (pintype "passive"))
      (node (ref "D3") (pin "1") (pinfunction "A_1") (pintype "passive"))
      (node (ref "D4") (pin "1") (pinfunction "A_1") (pintype "passive"))
      (node (ref "D5") (pin "1") (pinfunction "A_1") (pintype "passive"))
      (node (ref "D6") (pin "1") (pinfunction "A_1") (pintype "passive"))
      (node (ref "IC2") (pin "5") (pinfunction "GND_5") (pintype "power_in"))
      (node (ref "J1") (pin "2") (pinfunction "2_2") (pintype "passive"))
      (node (ref "J1") (pin "5") (pinfunction "5_5") (pintype "passive"))
      (node (ref "J10") (pin "5") (pinfunction "5_5") (pintype "passive"))
      (node (ref "J11") (pin "1") (pinfunction "1_1") (pintype "passive"))
      (node (ref "J12") (pin "4") (pinfunction "4_4") (pintype "passive"))
      (node (ref "J12") (pin "5") (pinfunction "5_5") (pintype "passive"))
      (node (ref "J2") (pin "1") (pinfunction "1_1") (pintype "passive"))
      (node (ref "J2") (pin "4") (pinfunction "4_4") (pintype "passive"))
      (node (ref "J3") (pin "6") (pinfunction "VSS_6") (pintype "power_in"))
      (node (ref "J3") (pin "CD2") (pinfunction "CD2_CD2") (pintype "bidirectional"))
      (node (ref "J3") (pin "SH1") (pinfunction "G3_SH1") (pintype "bidirectional"))
      (node (ref "J3") (pin "SH2") (pinfunction "G3_SH2") (pintype "bidirectional"))
      (node (ref "J3") (pin "SH3") (pinfunction "G2_SH3") (pintype "bidirectional"))
      (node (ref "J3") (pin "SH4") (pinfunction "G2_SH4") (pintype "bidirectional"))
      (node (ref "J4") (pin "13") (pinfunction "13_13") (pintype "bidirectional"))
      (node (ref "J4") (pin "14") (pinfunction "14_14") (pintype "bidirectional"))
      (node (ref "J4") (pin "8") (pinfunction "8_8") (pintype "bidirectional"))
      (node (ref "J5") (pin "1") (pinfunction "1_1") (pintype "passive"))
      (node (ref "J6") (pin "1") (pinfunction "1_1") (pintype "passive"))
      (node (ref "J7") (pin "5") (pinfunction "5_5") (pintype "passive"))
      (node (ref "J9") (pin "1") (pinfunction "1_1") (pintype "passive"))
      (node (ref "LED2") (pin "C") (pinfunction "C_C") (pintype "passive"))
      (node (ref "LED3") (pin "C") (pinfunction "C_C") (pintype "passive"))
      (node (ref "LED4") (pin "C") (pinfunction "C_C") (pintype "passive"))
      (node (ref "LED5") (pin "C") (pinfunction "C_C") (pintype "passive"))
      (node (ref "LPC1") (pin "1") (pinfunction "1_1") (pintype "passive"))
      (node (ref "LPC1") (pin "54") (pinfunction "54_54") (pintype "passive"))
      (node (ref "OC1") (pin "11") (pinfunction "EMIT_11") (pintype "passive"))
      (node (ref "OC1") (pin "13") (pinfunction "EMIT_13") (pintype "passive"))
      (node (ref "OC1") (pin "15") (pinfunction "EMIT_15") (pintype "passive"))
      (node (ref "OC1") (pin "9") (pinfunction "EMIT_9") (pintype "passive"))
      (node (ref "OC2") (pin "11") (pinfunction "EMIT_11") (pintype "passive"))
      (node (ref "OC2") (pin "13") (pinfunction "EMIT_13") (pintype "passive"))
      (node (ref "OC2") (pin "15") (pinfunction "EMIT_15") (pintype "passive"))
      (node (ref "OC2") (pin "9") (pinfunction "EMIT_9") (pintype "passive"))
      (node (ref "R1") (pin "1") (pinfunction "1_1") (pintype "passive"))
      (node (ref "U1") (pin "8") (pinfunction "E_8") (pintype "passive"))
      (node (ref "U2") (pin "8") (pinfunction "E_8") (pintype "passive"))
      (node (ref "USB1") (pin "5") (pinfunction "5_5") (pintype "input"))
      (node (ref "USB1") (pin "GND1") (pinfunction "GND1_GND1") (pintype "bidirectional"))
      (node (ref "USB1") (pin "GND2") (pinfunction "GND2_GND2") (pintype "bidirectional"))
      (node (ref "USB1") (pin "GND3") (pinfunction "GND3_GND3") (pintype "bidirectional"))
      (node (ref "USB1") (pin "GND4") (pinfunction "GND4_GND4") (pintype "bidirectional"))
      (node (ref "VR1") (pin "P2") (pinfunction "GND_P2") (pintype "bidirectional"))
    )
    (net (code "34") (name "Net-(C3-P$1)") (class "Default")
      (node (ref "C3") (pin "1") (pinfunction "P$1_1") (pintype "passive"))
      (node (ref "R13") (pin "2") (pinfunction "2_2") (pintype "passive"))
      (node (ref "R15") (pin "2") (pinfunction "2_2") (pintype "passive"))
      (node (ref "R17") (pin "2") (pinfunction "2_2") (pintype "passive"))
      (node (ref "R19") (pin "2") (pinfunction "2_2") (pintype "passive"))
      (node (ref "R7") (pin "1") (pinfunction "1_1") (pintype "passive"))
      (node (ref "R8") (pin "1") (pinfunction "1_1") (pintype "passive"))
      (node (ref "R9") (pin "1") (pinfunction "1_1") (pintype "passive"))
    )
    (net (code "35") (name "Net-(C4-P$1)") (class "Default")
      (node (ref "C4") (pin "1") (pinfunction "P$1_1") (pintype "passive"))
      (node (ref "R10") (pin "1") (pinfunction "1_1") (pintype "passive"))
      (node (ref "R11") (pin "1") (pinfunction "1_1") (pintype "passive"))
      (node (ref "R12") (pin "1") (pinfunction "1_1") (pintype "passive"))
      (node (ref "R14") (pin "2") (pinfunction "2_2") (pintype "passive"))
      (node (ref "R16") (pin "2") (pinfunction "2_2") (pintype "passive"))
      (node (ref "R18") (pin "2") (pinfunction "2_2") (pintype "passive"))
      (node (ref "R20") (pin "2") (pinfunction "2_2") (pintype "passive"))
    )
    (net (code "36") (name "Net-(C15-P$1)") (class "Default")
      (node (ref "C15") (pin "1") (pinfunction "P$1_1") (pintype "passive"))
      (node (ref "R39") (pin "1") (pinfunction "1_1") (pintype "passive"))
      (node (ref "R41") (pin "2") (pinfunction "2_2") (pintype "passive"))
    )
    (net (code "37") (name "Net-(C18-P$1)") (class "Default")
      (node (ref "C18") (pin "1") (pinfunction "P$1_1") (pintype "passive"))
      (node (ref "IC1") (pin "3") (pinfunction "+IN_3") (pintype "input"))
      (node (ref "R41") (pin "1") (pinfunction "1_1") (pintype "passive"))
    )
    (net (code "38") (name "Net-(LED1-PadC)") (class "Default")
      (node (ref "LED1") (pin "C") (pinfunction "C_C") (pintype "passive"))
      (node (ref "R1") (pin "2") (pinfunction "2_2") (pintype "passive"))
    )
    (net (code "39") (name "Net-(LED2-PadA)") (class "Default")
      (node (ref "LED2") (pin "A") (pinfunction "A_A") (pintype "passive"))
      (node (ref "R3") (pin "2") (pinfunction "2_2") (pintype "passive"))
    )
    (net (code "40") (name "Net-(LED3-PadA)") (class "Default")
      (node (ref "LED3") (pin "A") (pinfunction "A_A") (pintype "passive"))
      (node (ref "R4") (pin "2") (pinfunction "2_2") (pintype "passive"))
    )
    (net (code "41") (name "Net-(LED4-PadA)") (class "Default")
      (node (ref "LED4") (pin "A") (pinfunction "A_A") (pintype "passive"))
      (node (ref "R5") (pin "2") (pinfunction "2_2") (pintype "passive"))
    )
    (net (code "42") (name "Net-(LED5-PadA)") (class "Default")
      (node (ref "LED5") (pin "A") (pinfunction "A_A") (pintype "passive"))
      (node (ref "R6") (pin "2") (pinfunction "2_2") (pintype "passive"))
    )
    (net (code "43") (name "Net-(OC1A-A)") (class "Default")
      (node (ref "OC1") (pin "1") (pinfunction "A_1") (pintype "passive"))
      (node (ref "R19") (pin "1") (pinfunction "1_1") (pintype "passive"))
    )
    (net (code "44") (name "Net-(OC1A-COL)") (class "Default")
      (node (ref "OC1") (pin "16") (pinfunction "COL_16") (pintype "passive"))
      (node (ref "R22") (pin "1") (pinfunction "1_1") (pintype "passive"))
      (node (ref "R30") (pin "2") (pinfunction "2_2") (pintype "passive"))
    )
    (net (code "45") (name "Net-(OC1B-A)") (class "Default")
      (node (ref "OC1") (pin "3") (pinfunction "A_3") (pintype "passive"))
      (node (ref "R17") (pin "1") (pinfunction "1_1") (pintype "passive"))
    )
    (net (code "46") (name "Net-(OC1B-COL)") (class "Default")
      (node (ref "OC1") (pin "14") (pinfunction "COL_14") (pintype "passive"))
      (node (ref "R24") (pin "1") (pinfunction "1_1") (pintype "passive"))
      (node (ref "R31") (pin "2") (pinfunction "2_2") (pintype "passive"))
    )
    (net (code "47") (name "Net-(OC1C-A)") (class "Default")
      (node (ref "OC1") (pin "5") (pinfunction "A_5") (pintype "passive"))
      (node (ref "R15") (pin "1") (pinfunction "1_1") (pintype "passive"))
    )
    (net (code "48") (name "Net-(OC1C-COL)") (class "Default")
      (node (ref "OC1") (pin "12") (pinfunction "COL_12") (pintype "passive"))
      (node (ref "R26") (pin "1") (pinfunction "1_1") (pintype "passive"))
      (node (ref "R32") (pin "2") (pinfunction "2_2") (pintype "passive"))
    )
    (net (code "49") (name "Net-(OC1D-A)") (class "Default")
      (node (ref "OC1") (pin "7") (pinfunction "A_7") (pintype "passive"))
      (node (ref "R13") (pin "1") (pinfunction "1_1") (pintype "passive"))
    )
    (net (code "50") (name "Net-(OC1D-COL)") (class "Default")
      (node (ref "OC1") (pin "10") (pinfunction "COL_10") (pintype "passive"))
      (node (ref "R28") (pin "1") (pinfunction "1_1") (pintype "passive"))
      (node (ref "R33") (pin "2") (pinfunction "2_2") (pintype "passive"))
    )
    (net (code "51") (name "Net-(OC2A-A)") (class "Default")
      (node (ref "OC2") (pin "1") (pinfunction "A_1") (pintype "passive"))
      (node (ref "R20") (pin "1") (pinfunction "1_1") (pintype "passive"))
    )
    (net (code "52") (name "Net-(OC2A-COL)") (class "Default")
      (node (ref "OC2") (pin "16") (pinfunction "COL_16") (pintype "passive"))
      (node (ref "R21") (pin "1") (pinfunction "1_1") (pintype "passive"))
      (node (ref "R29") (pin "1") (pinfunction "1_1") (pintype "passive"))
    )
    (net (code "53") (name "Net-(OC2B-A)") (class "Default")
      (node (ref "OC2") (pin "3") (pinfunction "A_3") (pintype "passive"))
      (node (ref "R18") (pin "1") (pinfunction "1_1") (pintype "passive"))
    )
    (net (code "54") (name "Net-(OC2B-COL)") (class "Default")
      (node (ref "OC2") (pin "14") (pinfunction "COL_14") (pintype "passive"))
      (node (ref "R23") (pin "1") (pinfunction "1_1") (pintype "passive"))
      (node (ref "R34") (pin "1") (pinfunction "1_1") (pintype "passive"))
    )
    (net (code "55") (name "Net-(OC2C-A)") (class "Default")
      (node (ref "OC2") (pin "5") (pinfunction "A_5") (pintype "passive"))
      (node (ref "R16") (pin "1") (pinfunction "1_1") (pintype "passive"))
    )
    (net (code "56") (name "Net-(OC2C-COL)") (class "Default")
      (node (ref "OC2") (pin "12") (pinfunction "COL_12") (pintype "passive"))
      (node (ref "R25") (pin "1") (pinfunction "1_1") (pintype "passive"))
      (node (ref "R35") (pin "1") (pinfunction "1_1") (pintype "passive"))
    )
    (net (code "57") (name "Net-(OC2D-A)") (class "Default")
      (node (ref "OC2") (pin "7") (pinfunction "A_7") (pintype "passive"))
      (node (ref "R14") (pin "1") (pinfunction "1_1") (pintype "passive"))
    )
    (net (code "58") (name "Net-(OC2D-COL)") (class "Default")
      (node (ref "OC2") (pin "10") (pinfunction "COL_10") (pintype "passive"))
      (node (ref "R27") (pin "1") (pinfunction "1_1") (pintype "passive"))
      (node (ref "R36") (pin "1") (pinfunction "1_1") (pintype "passive"))
    )
    (net (code "59") (name "Net-(OC3-A)") (class "Default")
      (node (ref "OC3") (pin "1") (pinfunction "A_1") (pintype "passive"))
      (node (ref "R37") (pin "2") (pinfunction "2_2") (pintype "passive"))
    )
    (net (code "60") (name "Net-(OC3-EMIT)") (class "Default")
      (node (ref "OC3") (pin "3") (pinfunction "EMIT_3") (pintype "passive"))
      (node (ref "R38") (pin "2") (pinfunction "2_2") (pintype "passive"))
      (node (ref "R39") (pin "2") (pinfunction "2_2") (pintype "passive"))
    )
    (net (code "61") (name "Net-(U1-COM)") (class "Default")
      (node (ref "J10") (pin "4") (pinfunction "4_4") (pintype "passive"))
      (node (ref "U1") (pin "9") (pinfunction "COM_9") (pintype "passive"))
    )
    (net (code "62") (name "Net-(U2-COM)") (class "Default")
      (node (ref "J12") (pin "3") (pinfunction "3_3") (pintype "passive"))
      (node (ref "U2") (pin "9") (pinfunction "COM_9") (pintype "passive"))
    )
    (net (code "63") (name "Net-(VR1-VOUT)") (class "Default")
      (node (ref "D2") (pin "A") (pinfunction "A_A") (pintype "passive"))
      (node (ref "VR1") (pin "P1") (pinfunction "VOUT_P1") (pintype "bidirectional"))
    )
    (net (code "64") (name "P0.0") (class "Default")
      (node (ref "IC2") (pin "1") (pinfunction "RO_1") (pintype "output"))
      (node (ref "LPC1") (pin "9") (pinfunction "9_9") (pintype "passive"))
    )
    (net (code "65") (name "P0.1") (class "Default")
      (node (ref "IC2") (pin "4") (pinfunction "DI_4") (pintype "input"))
      (node (ref "LPC1") (pin "10") (pinfunction "10_10") (pintype "passive"))
    )
    (net (code "66") (name "P0.2") (class "Default")
      (node (ref "AUX3") (pin "2") (pinfunction "2_2") (pintype "passive"))
      (node (ref "LPC1") (pin "21") (pinfunction "21_21") (pintype "passive"))
    )
    (net (code "67") (name "P0.3") (class "Default")
      (node (ref "AUX3") (pin "1") (pinfunction "1_1") (pintype "passive"))
      (node (ref "LPC1") (pin "22") (pinfunction "22_22") (pintype "passive"))
    )
    (net (code "68") (name "P0.4") (class "Default")
      (node (ref "LPC1") (pin "38") (pinfunction "38_38") (pintype "passive"))
      (node (ref "U1") (pin "1") (pinfunction "1B_1") (pintype "input"))
    )
    (net (code "69") (name "P0.5") (class "Default")
      (node (ref "LPC1") (pin "39") (pinfunction "39_39") (pintype "passive"))
      (node (ref "U1") (pin "2") (pinfunction "2B_2") (pintype "input"))
    )
    (net (code "70") (name "P0.6") (class "Default")
      (node (ref "J3") (pin "2") (pinfunction "CD/DAT3_2") (pintype "bidirectional"))
      (node (ref "LPC1") (pin "8") (pinfunction "8_8") (pintype "passive"))
      (node (ref "R2") (pin "1") (pinfunction "1_1") (pintype "passive"))
    )
    (net (code "71") (name "P0.7") (class "Default")
      (node (ref "J3") (pin "5") (pinfunction "CLK_5") (pintype "bidirectional"))
      (node (ref "LPC1") (pin "7") (pinfunction "7_7") (pintype "passive"))
    )
    (net (code "72") (name "P0.8") (class "Default")
      (node (ref "J3") (pin "7") (pinfunction "DAT0_7") (pintype "bidirectional"))
      (node (ref "LPC1") (pin "6") (pinfunction "6_6") (pintype "passive"))
    )
    (net (code "73") (name "P0.9") (class "Default")
      (node (ref "J3") (pin "3") (pinfunction "CMD_3") (pintype "bidirectional"))
      (node (ref "LPC1") (pin "5") (pinfunction "5_5") (pintype "passive"))
    )
    (net (code "74") (name "P0.10") (class "Default")
      (node (ref "LPC1") (pin "40") (pinfunction "40_40") (pintype "passive"))
      (node (ref "U1") (pin "3") (pinfunction "3B_3") (pintype "input"))
    )
    (net (code "75") (name "P0.11") (class "Default")
      (node (ref "LPC1") (pin "41") (pinfunction "41_41") (pintype "passive"))
      (node (ref "U1") (pin "4") (pinfunction "4B_4") (pintype "input"))
    )
    (net (code "76") (name "P0.15") (class "Default")
      (node (ref "AUX3") (pin "7") (pinfunction "7_7") (pintype "passive"))
      (node (ref "LPC1") (pin "13") (pinfunction "13_13") (pintype "passive"))
    )
    (net (code "77") (name "P0.16") (class "Default")
      (node (ref "AUX3") (pin "8") (pinfunction "8_8") (pintype "passive"))
      (node (ref "LPC1") (pin "14") (pinfunction "14_14") (pintype "passive"))
    )
    (net (code "78") (name "P0.17") (class "Default")
      (node (ref "AUX3") (pin "5") (pinfunction "5_5") (pintype "passive"))
      (node (ref "LPC1") (pin "12") (pinfunction "12_12") (pintype "passive"))
    )
    (net (code "79") (name "P0.18") (class "Default")
      (node (ref "AUX3") (pin "6") (pinfunction "6_6") (pintype "passive"))
      (node (ref "LPC1") (pin "11") (pinfunction "11_11") (pintype "passive"))
    )
    (net (code "80") (name "P0.21") (class "Default")
      (node (ref "IC2") (pin "2") (pinfunction "RE/_2") (pintype "input"))
      (node (ref "IC2") (pin "3") (pinfunction "DE_3") (pintype "input"))
      (node (ref "LPC1") (pin "23") (pinfunction "23_23") (pintype "passive"))
    )
    (net (code "81") (name "P0.23") (class "Default")
      (node (ref "C22") (pin "1") (pinfunction "P$1_1") (pintype "passive"))
      (node (ref "D6") (pin "3") (pinfunction "AC_3") (pintype "passive"))
      (node (ref "LPC1") (pin "15") (pinfunction "15_15") (pintype "passive"))
      (node (ref "R48") (pin "1") (pinfunction "1_1") (pintype "passive"))
    )
    (net (code "82") (name "P0.24") (class "Default")
      (node (ref "C21") (pin "1") (pinfunction "P$1_1") (pintype "passive"))
      (node (ref "D5") (pin "3") (pinfunction "AC_3") (pintype "passive"))
      (node (ref "LPC1") (pin "16") (pinfunction "16_16") (pintype "passive"))
      (node (ref "R47") (pin "1") (pinfunction "1_1") (pintype "passive"))
    )
    (net (code "83") (name "P0.25") (class "Default")
      (node (ref "C20") (pin "1") (pinfunction "P$1_1") (pintype "passive"))
      (node (ref "D4") (pin "3") (pinfunction "AC_3") (pintype "passive"))
      (node (ref "LPC1") (pin "17") (pinfunction "17_17") (pintype "passive"))
      (node (ref "R46") (pin "1") (pinfunction "1_1") (pintype "passive"))
    )
    (net (code "84") (name "P0.26") (class "Default")
      (node (ref "C19") (pin "1") (pinfunction "P$1_1") (pintype "passive"))
      (node (ref "D3") (pin "3") (pinfunction "AC_3") (pintype "passive"))
      (node (ref "LPC1") (pin "18") (pinfunction "18_18") (pintype "passive"))
      (node (ref "R45") (pin "1") (pinfunction "1_1") (pintype "passive"))
    )
    (net (code "85") (name "P1.18") (class "Default")
      (node (ref "LPC1") (pin "73") (pinfunction "73_73") (pintype "passive"))
      (node (ref "R3") (pin "1") (pinfunction "1_1") (pintype "passive"))
    )
    (net (code "86") (name "P1.19") (class "Default")
      (node (ref "LPC1") (pin "72") (pinfunction "72_72") (pintype "passive"))
      (node (ref "R4") (pin "1") (pinfunction "1_1") (pintype "passive"))
    )
    (net (code "87") (name "P1.20") (class "Default")
      (node (ref "LPC1") (pin "71") (pinfunction "71_71") (pintype "passive"))
      (node (ref "R5") (pin "1") (pinfunction "1_1") (pintype "passive"))
    )
    (net (code "88") (name "P1.21") (class "Default")
      (node (ref "LPC1") (pin "70") (pinfunction "70_70") (pintype "passive"))
      (node (ref "R6") (pin "1") (pinfunction "1_1") (pintype "passive"))
    )
    (net (code "89") (name "P1.22") (class "Default")
      (node (ref "AUX2") (pin "4") (pinfunction "4_4") (pintype "passive"))
      (node (ref "LPC1") (pin "69") (pinfunction "69_69") (pintype "passive"))
    )
    (net (code "90") (name "P1.23") (class "Default")
      (node (ref "C10") (pin "1") (pinfunction "P$1_1") (pintype "passive"))
      (node (ref "LPC1") (pin "68") (pinfunction "68_68") (pintype "passive"))
      (node (ref "R33") (pin "1") (pinfunction "1_1") (pintype "passive"))
    )
    (net (code "91") (name "P1.24") (class "Default")
      (node (ref "C9") (pin "1") (pinfunction "P$1_1") (pintype "passive"))
      (node (ref "LPC1") (pin "67") (pinfunction "67_67") (pintype "passive"))
      (node (ref "R32") (pin "1") (pinfunction "1_1") (pintype "passive"))
    )
    (net (code "92") (name "P1.25") (class "Default")
      (node (ref "C8") (pin "1") (pinfunction "P$1_1") (pintype "passive"))
      (node (ref "LPC1") (pin "66") (pinfunction "66_66") (pintype "passive"))
      (node (ref "R31") (pin "1") (pinfunction "1_1") (pintype "passive"))
    )
    (net (code "93") (name "P1.26") (class "Default")
      (node (ref "C7") (pin "1") (pinfunction "P$1_1") (pintype "passive"))
      (node (ref "LPC1") (pin "65") (pinfunction "65_65") (pintype "passive"))
      (node (ref "R30") (pin "1") (pinfunction "1_1") (pintype "passive"))
    )
    (net (code "94") (name "P1.27") (class "Default")
      (node (ref "AUX2") (pin "5") (pinfunction "5_5") (pintype "passive"))
      (node (ref "LPC1") (pin "64") (pinfunction "64_64") (pintype "passive"))
    )
    (net (code "95") (name "P1.28") (class "Default")
      (node (ref "C14") (pin "1") (pinfunction "P$1_1") (pintype "passive"))
      (node (ref "LPC1") (pin "63") (pinfunction "63_63") (pintype "passive"))
      (node (ref "R36") (pin "2") (pinfunction "2_2") (pintype "passive"))
    )
    (net (code "96") (name "P1.29") (class "Default")
      (node (ref "C13") (pin "1") (pinfunction "P$1_1") (pintype "passive"))
      (node (ref "LPC1") (pin "62") (pinfunction "62_62") (pintype "passive"))
      (node (ref "R35") (pin "2") (pinfunction "2_2") (pintype "passive"))
    )
    (net (code "97") (name "P1.30") (class "Default")
      (node (ref "AUX2") (pin "1") (pinfunction "1_1") (pintype "passive"))
      (node (ref "LPC1") (pin "19") (pinfunction "19_19") (pintype "passive"))
    )
    (net (code "98") (name "P1.31") (class "Default")
      (node (ref "C12") (pin "1") (pinfunction "P$1_1") (pintype "passive"))
      (node (ref "LPC1") (pin "20") (pinfunction "20_20") (pintype "passive"))
      (node (ref "R34") (pin "2") (pinfunction "2_2") (pintype "passive"))
    )
    (net (code "99") (name "P2.0") (class "Default")
      (node (ref "LPC1") (pin "42") (pinfunction "42_42") (pintype "passive"))
      (node (ref "U1") (pin "5") (pinfunction "5B_5") (pintype "input"))
    )
    (net (code "100") (name "P2.1") (class "Default")
      (node (ref "LPC1") (pin "43") (pinfunction "43_43") (pintype "passive"))
      (node (ref "U1") (pin "6") (pinfunction "6B_6") (pintype "input"))
    )
    (net (code "101") (name "P2.2") (class "Default")
      (node (ref "LPC1") (pin "44") (pinfunction "44_44") (pintype "passive"))
      (node (ref "U1") (pin "7") (pinfunction "7B_7") (pintype "input"))
    )
    (net (code "102") (name "P2.3") (class "Default")
      (node (ref "LPC1") (pin "45") (pinfunction "45_45") (pintype "passive"))
      (node (ref "U2") (pin "1") (pinfunction "1B_1") (pintype "input"))
    )
    (net (code "103") (name "P2.4") (class "Default")
      (node (ref "LPC1") (pin "46") (pinfunction "46_46") (pintype "passive"))
      (node (ref "U2") (pin "2") (pinfunction "2B_2") (pintype "input"))
    )
    (net (code "104") (name "P2.5") (class "Default")
      (node (ref "LPC1") (pin "47") (pinfunction "47_47") (pintype "passive"))
      (node (ref "U2") (pin "7") (pinfunction "7B_7") (pintype "input"))
    )
    (net (code "105") (name "P2.6") (class "Default")
      (node (ref "LPC1") (pin "48") (pinfunction "48_48") (pintype "passive"))
      (node (ref "U2") (pin "6") (pinfunction "6B_6") (pintype "input"))
    )
    (net (code "106") (name "P2.7") (class "Default")
      (node (ref "LPC1") (pin "49") (pinfunction "49_49") (pintype "passive"))
      (node (ref "U2") (pin "5") (pinfunction "5B_5") (pintype "input"))
    )
    (net (code "107") (name "P2.8") (class "Default")
      (node (ref "LPC1") (pin "50") (pinfunction "50_50") (pintype "passive"))
      (node (ref "U2") (pin "4") (pinfunction "4B_4") (pintype "input"))
    )
    (net (code "108") (name "P2.11") (class "Default")
      (node (ref "LPC1") (pin "52") (pinfunction "52_52") (pintype "passive"))
      (node (ref "U2") (pin "3") (pinfunction "3B_3") (pintype "input"))
    )
    (net (code "109") (name "P2.12") (class "Default")
      (node (ref "AUX2") (pin "6") (pinfunction "6_6") (pintype "passive"))
      (node (ref "LPC1") (pin "53") (pinfunction "53_53") (pintype "passive"))
    )
    (net (code "110") (name "P2.13") (class "Default")
      (node (ref "C11") (pin "1") (pinfunction "P$1_1") (pintype "passive"))
      (node (ref "LPC1") (pin "27") (pinfunction "27_27") (pintype "passive"))
      (node (ref "R29") (pin "2") (pinfunction "2_2") (pintype "passive"))
    )
    (net (code "111") (name "P4.28") (class "Default")
      (node (ref "AUX2") (pin "7") (pinfunction "7_7") (pintype "passive"))
      (node (ref "LPC1") (pin "59") (pinfunction "59_59") (pintype "passive"))
    )
    (net (code "112") (name "P4.29") (class "Default")
      (node (ref "AUX2") (pin "2") (pinfunction "2_2") (pintype "passive"))
      (node (ref "LPC1") (pin "58") (pinfunction "58_58") (pintype "passive"))
    )
    (net (code "113") (name "PWMA") (class "Default")
      (node (ref "OC3") (pin "2") (pinfunction "C_2") (pintype "passive"))
      (node (ref "U2") (pin "10") (pinfunction "7C_10") (pintype "output"))
    )
    (net (code "114") (name "RESET") (class "Default")
      (node (ref "AUX2") (pin "3") (pinfunction "3_3") (pintype "passive"))
      (node (ref "LPC1") (pin "4") (pinfunction "4_4") (pintype "passive"))
    )
    (net (code "115") (name "RS485A") (class "Default")
      (node (ref "IC2") (pin "6") (pinfunction "A_6") (pintype "passive"))
      (node (ref "J8") (pin "1") (pinfunction "1_1") (pintype "passive"))
      (node (ref "R49") (pin "1") (pinfunction "1_1") (pintype "passive"))
    )
    (net (code "116") (name "RS485B") (class "Default")
      (node (ref "IC2") (pin "7") (pinfunction "B_7") (pintype "passive"))
      (node (ref "J8") (pin "2") (pinfunction "2_2") (pintype "passive"))
      (node (ref "R49") (pin "2") (pinfunction "2_2") (pintype "passive"))
    )
    (net (code "117") (name "SGND") (class "Default")
      (node (ref "C15") (pin "2") (pinfunction "P$2_2") (pintype "passive"))
      (node (ref "C16") (pin "2") (pinfunction "P$2_2") (pintype "passive"))
      (node (ref "C17") (pin "2") (pinfunction "P$2_2") (pintype "passive"))
      (node (ref "C18") (pin "2") (pinfunction "P$2_2") (pintype "passive"))
      (node (ref "IC1") (pin "2") (pinfunction "V-_2") (pintype "power_in"))
      (node (ref "J8") (pin "5") (pinfunction "5_5") (pintype "passive"))
      (node (ref "R38") (pin "1") (pinfunction "1_1") (pintype "passive"))
    )
    (net (code "118") (name "SIN") (class "Default")
      (node (ref "C16") (pin "1") (pinfunction "P$1_1") (pintype "passive"))
      (node (ref "C17") (pin "1") (pinfunction "P$1_1") (pintype "passive"))
      (node (ref "IC1") (pin "5") (pinfunction "V+_5") (pintype "power_in"))
      (node (ref "J8") (pin "3") (pinfunction "3_3") (pintype "passive"))
      (node (ref "OC3") (pin "4") (pinfunction "COL_4") (pintype "passive"))
    )
    (net (code "119") (name "SOUT") (class "Default")
      (node (ref "IC1") (pin "1") (pinfunction "OUT_1") (pintype "output"))
      (node (ref "IC1") (pin "4") (pinfunction "-IN_4") (pintype "input"))
      (node (ref "J8") (pin "4") (pinfunction "4_4") (pintype "passive"))
    )
    (net (code "120") (name "UDM") (class "Default")
      (node (ref "LPC1") (pin "36") (pinfunction "36_36") (pintype "passive"))
      (node (ref "USB1") (pin "2") (pinfunction "2_2") (pintype "input"))
    )
    (net (code "121") (name "UDP") (class "Default")
      (node (ref "LPC1") (pin "37") (pinfunction "37_37") (pintype "passive"))
      (node (ref "USB1") (pin "3") (pinfunction "3_3") (pintype "input"))
    )
    (net (code "122") (name "VUSB") (class "Default")
      (node (ref "D1") (pin "A") (pinfunction "A_A") (pintype "passive"))
      (node (ref "USB1") (pin "1") (pinfunction "1_1") (pintype "input"))
    )
    (net (code "123") (name "unconnected-(AUX2-Pad8)") (class "Default")
      (node (ref "AUX2") (pin "8") (pinfunction "8_8") (pintype "passive"))
    )
    (net (code "124") (name "unconnected-(AUX3-Pad3)") (class "Default")
      (node (ref "AUX3") (pin "3") (pinfunction "3_3") (pintype "passive"))
    )
    (net (code "125") (name "unconnected-(AUX3-Pad4)") (class "Default")
      (node (ref "AUX3") (pin "4") (pinfunction "4_4") (pintype "passive"))
    )
    (net (code "126") (name "unconnected-(AUX3-Pad9)") (class "Default")
      (node (ref "AUX3") (pin "9") (pinfunction "9_9") (pintype "passive"))
    )
    (net (code "127") (name "unconnected-(AUX3-Pad10)") (class "Default")
      (node (ref "AUX3") (pin "10") (pinfunction "10_10") (pintype "passive"))
    )
    (net (code "128") (name "unconnected-(J3-DAT1-Pad8)") (class "Default")
      (node (ref "J3") (pin "8") (pinfunction "DAT1_8") (pintype "bidirectional"))
    )
    (net (code "129") (name "unconnected-(J3-DATA2-Pad1)") (class "Default")
      (node (ref "J3") (pin "1") (pinfunction "DATA2_1") (pintype "bidirectional"))
    )
    (net (code "130") (name "unconnected-(J3-PadCD1)") (class "Default")
      (node (ref "J3") (pin "CD1") (pinfunction "CD1_CD1") (pintype "bidirectional"))
    )
    (net (code "131") (name "unconnected-(J4-Pad9)") (class "Default")
      (node (ref "J4") (pin "9") (pinfunction "9_9") (pintype "bidirectional"))
    )
    (net (code "132") (name "unconnected-(J4-Pad10)") (class "Default")
      (node (ref "J4") (pin "10") (pinfunction "10_10") (pintype "bidirectional"))
    )
    (net (code "133") (name "unconnected-(J4-Pad11)") (class "Default")
      (node (ref "J4") (pin "11") (pinfunction "11_11") (pintype "bidirectional"))
    )
    (net (code "134") (name "unconnected-(J4-Pad12)") (class "Default")
      (node (ref "J4") (pin "12") (pinfunction "12_12") (pintype "bidirectional"))
    )
    (net (code "135") (name "unconnected-(LPC1-Pad3)") (class "Default")
      (node (ref "LPC1") (pin "3") (pinfunction "3_3") (pintype "passive"))
    )
    (net (code "136") (name "unconnected-(LPC1-Pad24)") (class "Default")
      (node (ref "LPC1") (pin "24") (pinfunction "24_24") (pintype "passive"))
    )
    (net (code "137") (name "unconnected-(LPC1-Pad25)") (class "Default")
      (node (ref "LPC1") (pin "25") (pinfunction "25_25") (pintype "passive"))
    )
    (net (code "138") (name "unconnected-(LPC1-Pad26)") (class "Default")
      (node (ref "LPC1") (pin "26") (pinfunction "26_26") (pintype "passive"))
    )
    (net (code "139") (name "unconnected-(LPC1-Pad29)") (class "Default")
      (node (ref "LPC1") (pin "29") (pinfunction "29_29") (pintype "passive"))
    )
    (net (code "140") (name "unconnected-(LPC1-Pad30)") (class "Default")
      (node (ref "LPC1") (pin "30") (pinfunction "30_30") (pintype "passive"))
    )
    (net (code "141") (name "unconnected-(LPC1-Pad31)") (class "Default")
      (node (ref "LPC1") (pin "31") (pinfunction "31_31") (pintype "passive"))
    )
    (net (code "142") (name "unconnected-(LPC1-Pad51)") (class "Default")
      (node (ref "LPC1") (pin "51") (pinfunction "51_51") (pintype "passive"))
    )
    (net (code "143") (name "unconnected-(LPC1-Pad55)") (class "Default")
      (node (ref "LPC1") (pin "55") (pinfunction "55_55") (pintype "passive"))
    )
    (net (code "144") (name "unconnected-(LPC1-Pad56)") (class "Default")
      (node (ref "LPC1") (pin "56") (pinfunction "56_56") (pintype "passive"))
    )
    (net (code "145") (name "unconnected-(LPC1-Pad57)") (class "Default")
      (node (ref "LPC1") (pin "57") (pinfunction "57_57") (pintype "passive"))
    )
    (net (code "146") (name "unconnected-(LPC1-Pad60)") (class "Default")
      (node (ref "LPC1") (pin "60") (pinfunction "60_60") (pintype "passive"))
    )
    (net (code "147") (name "unconnected-(LPC1-Pad61)") (class "Default")
      (node (ref "LPC1") (pin "61") (pinfunction "61_61") (pintype "passive"))
    )
    (net (code "148") (name "unconnected-(USB1-Pad4)") (class "Default")
      (node (ref "USB1") (pin "4") (pinfunction "4_4") (pintype "input"))
    )
  )
)
